# PWMfilterSims.net
KiCad netlist of a schematic drawn in Altium Designer
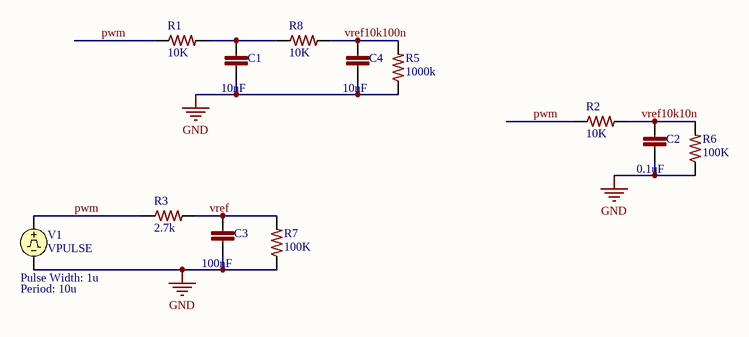
[diagram p0: PWMfilterSims.SchDoc]

(export (version "E")
  (design (tool "Eeschema 10.0.6"))
  (components
    (comp (ref "C1")
      (value "10nF")
      (footprint "C0402")
      (description "CAP CER 0402 1uF 6.3V 10% X5R")
      (fields
        (field (name "MANUFACTURERPARTNUMBER") "GRM155R60J105KE19D")
        (field (name "PUBLISHER") "UltiMachine")
      )
      (libsource (lib "3Delight") (part "GRM155R60J105KE19D"))
    )
    (comp (ref "C2")
      (value "0.1uF")
      (footprint "C0402")
      (description "CAP CER 0402 1uF 6.3V 10% X5R")
      (fields
        (field (name "MANUFACTURERPARTNUMBER") "GRM155R60J105KE19D")
        (field (name "PUBLISHER") "UltiMachine")
      )
      (libsource (lib "3Delight") (part "GRM155R60J105KE19D"))
    )
    (comp (ref "C3")
      (value "100nF")
      (footprint "C0402")
      (description "CAP CER 0402 1uF 6.3V 10% X5R")
      (fields
        (field (name "MANUFACTURERPARTNUMBER") "GRM155R60J105KE19D")
        (field (name "PUBLISHER") "UltiMachine")
      )
      (libsource (lib "3Delight") (part "GRM155R60J105KE19D"))
    )
    (comp (ref "C4")
      (value "10nF")
      (footprint "C0402")
      (description "CAP CER 0402 1uF 6.3V 10% X5R")
      (fields
        (field (name "MANUFACTURERPARTNUMBER") "GRM155R60J105KE19D")
        (field (name "PUBLISHER") "UltiMachine")
      )
      (libsource (lib "3Delight") (part "GRM155R60J105KE19D"))
    )
    (comp (ref "R1")
      (value "10K")
      (footprint "R0603")
      (description "RES 0603 10K 100mW 1%")
      (fields
        (field (name "MANUFACTURERPARTNUMBER") "ERJ-3EKF1002V")
        (field (name "PUBLISHER") "UltiMachine")
      )
      (libsource (lib "3Delight") (part "ERJ-3EKF1002V"))
    )
    (comp (ref "R2")
      (value "10K")
      (footprint "R0603")
      (description "RES 0603 10K 100mW 1%")
      (fields
        (field (name "MANUFACTURERPARTNUMBER") "ERJ-3EKF1002V")
        (field (name "PUBLISHER") "UltiMachine")
      )
      (libsource (lib "3Delight") (part "ERJ-3EKF1002V"))
    )
    (comp (ref "R3")
      (value "2.7k")
      (footprint "R0603")
      (description "RES 0603 10K 100mW 1%")
      (fields
        (field (name "MANUFACTURERPARTNUMBER") "ERJ-3EKF1002V")
        (field (name "PUBLISHER") "UltiMachine")
      )
      (libsource (lib "3Delight") (part "ERJ-3EKF1002V"))
    )
    (comp (ref "R5")
      (value "1000k")
      (footprint "R0603")
      (description "RES 100K OHM 1/10W 1% 0603 SMD")
      (fields
        (field (name "MANUFACTURERPARTNUMBER") "RC0603FR-07100KL")
        (field (name "PUBLISHER") "UltiMachine")
      )
      (libsource (lib "3Delight") (part "RC0603FR-07100KL"))
    )
    (comp (ref "R6")
      (value "100K")
      (footprint "R0603")
      (description "RES 100K OHM 1/10W 1% 0603 SMD")
      (fields
        (field (name "MANUFACTURERPARTNUMBER") "RC0603FR-07100KL")
        (field (name "PUBLISHER") "UltiMachine")
      )
      (libsource (lib "3Delight") (part "RC0603FR-07100KL"))
    )
    (comp (ref "R7")
      (value "100K")
      (footprint "R0603")
      (description "RES 100K OHM 1/10W 1% 0603 SMD")
      (fields
        (field (name "MANUFACTURERPARTNUMBER") "RC0603FR-07100KL")
        (field (name "PUBLISHER") "UltiMachine")
      )
      (libsource (lib "3Delight") (part "RC0603FR-07100KL"))
    )
    (comp (ref "R8")
      (value "10K")
      (footprint "R0603")
      (description "RES 0603 10K 100mW 1%")
      (fields
        (field (name "MANUFACTURERPARTNUMBER") "ERJ-3EKF1002V")
        (field (name "PUBLISHER") "UltiMachine")
      )
      (libsource (lib "3Delight") (part "ERJ-3EKF1002V"))
    )
    (comp (ref "V1")
      (value "VPULSE")
      (description "Pulse Voltage Source")
      (fields
        (field (name "PULSE WIDTH") "1u")
        (field (name "PERIOD") "10u")
        (field (name "PUBLISHER") "Altium Limited")
      )
      (libsource (lib "Simulation Sources") (part "VPULSE"))
    )
  )
  (nets
    (net (code "1") (name "/pwm") (class "Default")
      (node (ref "R1") (pin "1") (pinfunction "1_1") (pintype "passive"))
      (node (ref "R2") (pin "1") (pinfunction "1_1") (pintype "passive"))
      (node (ref "R3") (pin "1") (pinfunction "1_1") (pintype "passive"))
      (node (ref "V1") (pin "1") (pinfunction "1_1") (pintype "passive"))
    )
    (net (code "2") (name "/vref") (class "Default")
      (node (ref "C3") (pin "1") (pinfunction "1_1") (pintype "passive"))
      (node (ref "R3") (pin "2") (pinfunction "2_2") (pintype "passive"))
      (node (ref "R7") (pin "2") (pinfunction "2_2") (pintype "passive"))
    )
    (net (code "3") (name "/vref10k10n") (class "Default")
      (node (ref "C2") (pin "1") (pinfunction "1_1") (pintype "passive"))
      (node (ref "R2") (pin "2") (pinfunction "2_2") (pintype "passive"))
      (node (ref "R6") (pin "2") (pinfunction "2_2") (pintype "passive"))
    )
    (net (code "4") (name "/vref10k100n") (class "Default")
      (node (ref "C4") (pin "1") (pinfunction "1_1") (pintype "passive"))
      (node (ref "R5") (pin "2") (pinfunction "2_2") (pintype "passive"))
      (node (ref "R8") (pin "2") (pinfunction "2_2") (pintype "passive"))
    )
    (net (code "5") (name "GND") (class "Default")
      (node (ref "C1") (pin "2") (pinfunction "2_2") (pintype "passive"))
      (node (ref "C2") (pin "2") (pinfunction "2_2") (pintype "passive"))
      (node (ref "C3") (pin "2") (pinfunction "2_2") (pintype "passive"))
      (node (ref "C4") (pin "2") (pinfunction "2_2") (pintype "passive"))
      (node (ref "R5") (pin "1") (pinfunction "1_1") (pintype "passive"))
      (node (ref "R6") (pin "1") (pinfunction "1_1") (pintype "passive"))
      (node (ref "R7") (pin "1") (pinfunction "1_1") (pintype "passive"))
      (node (ref "V1") (pin "2") (pinfunction "2_2") (pintype "passive"))
    )
    (net (code "6") (name "Net-(C1-Pad1)") (class "Default")
      (node (ref "C1") (pin "1") (pinfunction "1_1") (pintype "passive"))
      (node (ref "R1") (pin "2") (pinfunction "2_2") (pintype "passive"))
      (node (ref "R8") (pin "1") (pinfunction "1_1") (pintype "passive"))
    )
  )
)
